# SparkFun_SOIC28-DIP-Adapter-v10.net
KiCad netlist of a schematic drawn in EAGLE
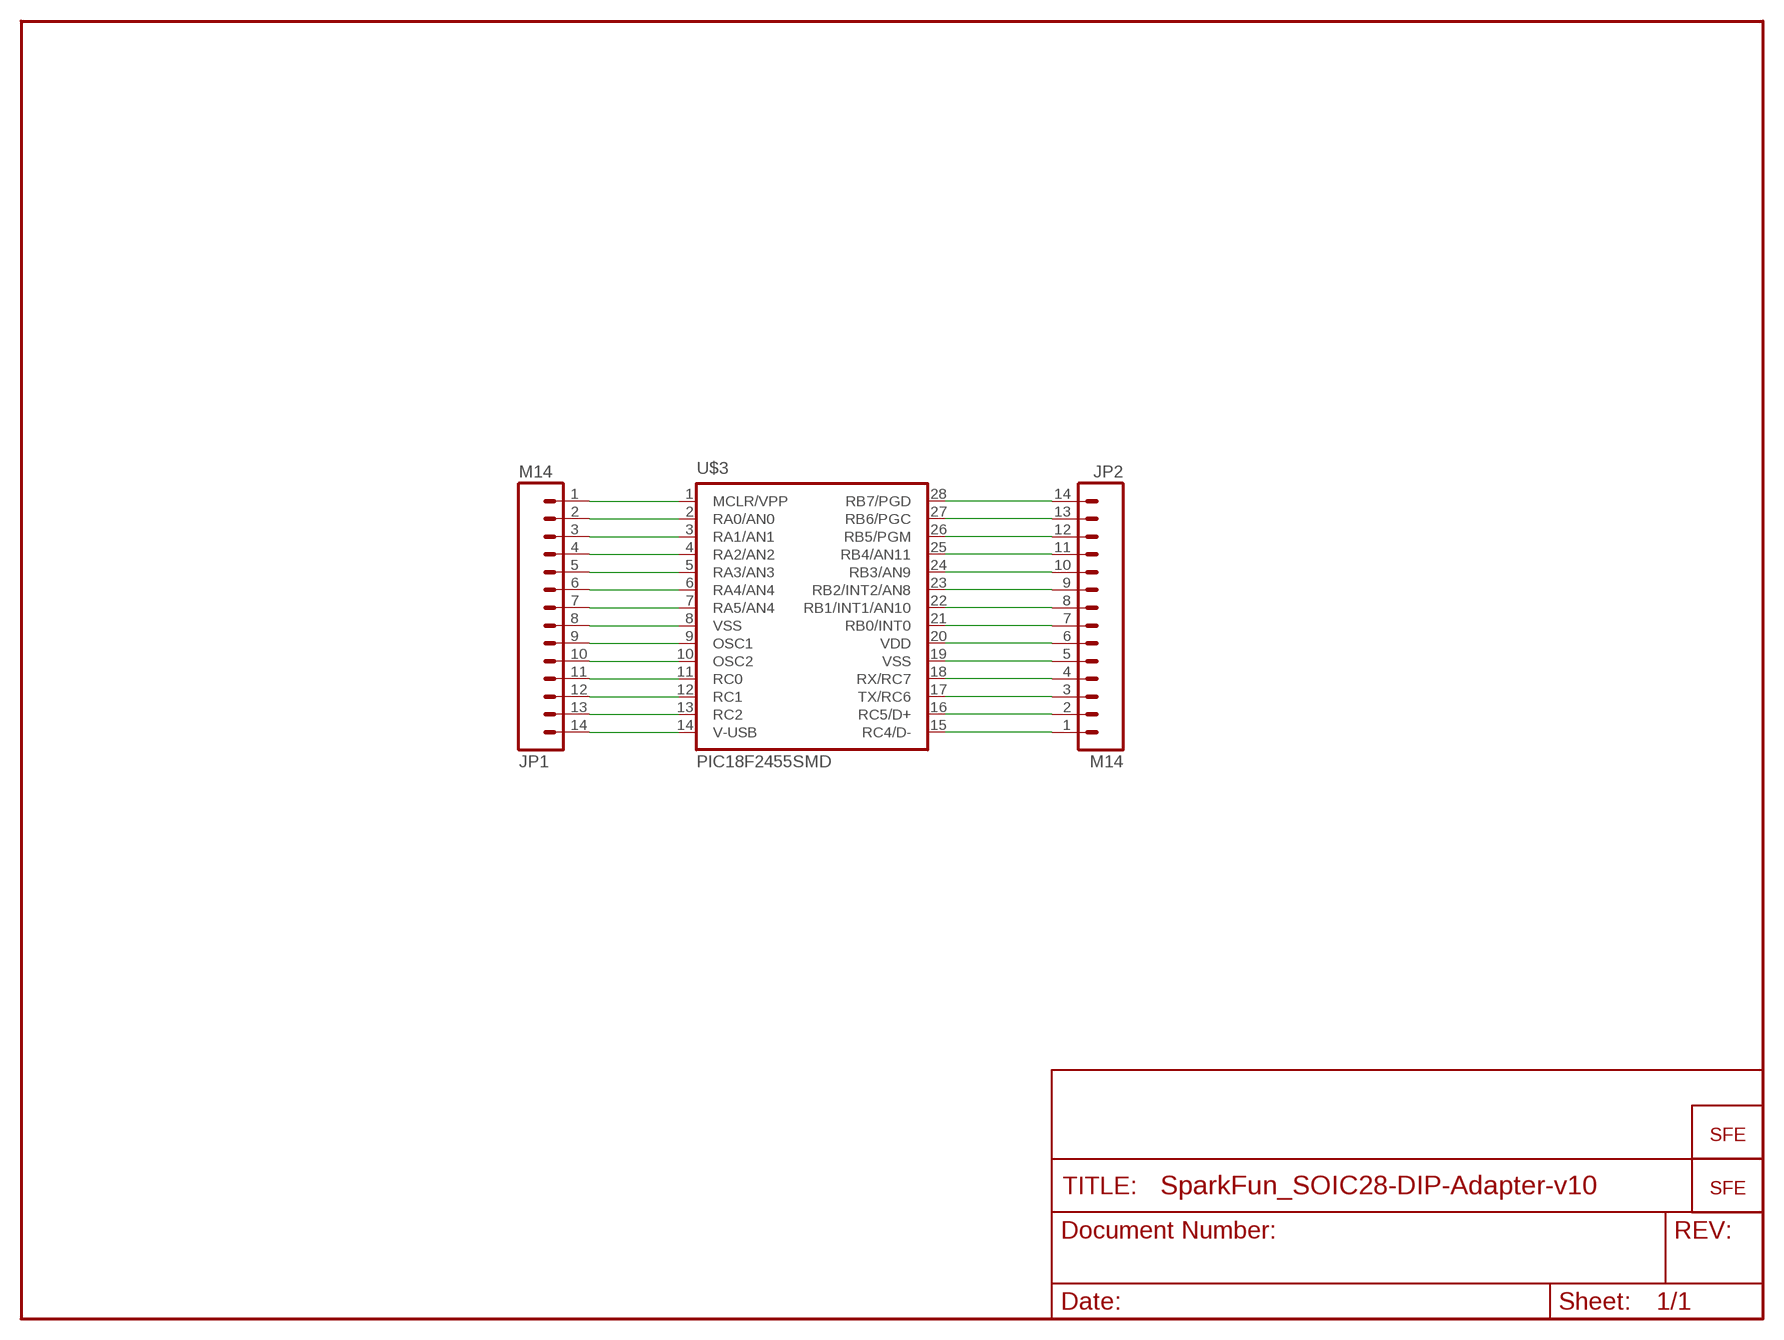
[diagram p0: schematic, sheet 1]

(export (version "E")
  (design (tool "Eeschema 10.0.6"))
  (components
    (comp (ref "JP1")
      (value "M14")
      (footprint "eagle-import:1X14")
      (libsource (lib "eagle-import") (part "M14"))
    )
    (comp (ref "JP2")
      (value "M14")
      (footprint "eagle-import:1X14")
      (libsource (lib "eagle-import") (part "M14"))
    )
    (comp (ref "U$1")
      (value "LOGO-SFESK")
      (footprint "eagle-import:SFE-LOGO-FLAME")
      (libsource (lib "eagle-import") (part "LOGO-SFESK"))
    )
    (comp (ref "U$2")
      (value "LOGO-SFENEW")
      (footprint "eagle-import:SFE-NEW-WEBLOGO")
      (libsource (lib "eagle-import") (part "LOGO-SFENEW"))
    )
    (comp (ref "U$3")
      (value "PIC18F2455SMD")
      (footprint "eagle-import:SO-28W")
      (libsource (lib "eagle-import") (part "PIC18F2455SMD"))
    )
  )
  (nets
    (net (code "1") (name "Net-(JP1-Pad8)") (class "Default")
      (node (ref "JP1") (pin "8") (pinfunction "8_8") (pintype "passive"))
      (node (ref "U$3") (pin "8") (pinfunction "VSS_8") (pintype "power_in"))
    )
    (net (code "2") (name "Net-(JP2-Pad5)") (class "Default")
      (node (ref "JP2") (pin "5") (pinfunction "5_5") (pintype "passive"))
      (node (ref "U$3") (pin "19") (pinfunction "VSS_19") (pintype "power_in"))
    )
    (net (code "3") (name "Net-(U$3-MCLR{slash}VPP)") (class "Default")
      (node (ref "JP1") (pin "1") (pinfunction "1_1") (pintype "passive"))
      (node (ref "U$3") (pin "1") (pinfunction "MCLR/VPP_1") (pintype "bidirectional"))
    )
    (net (code "4") (name "Net-(U$3-OSC1)") (class "Default")
      (node (ref "JP1") (pin "9") (pinfunction "9_9") (pintype "passive"))
      (node (ref "U$3") (pin "9") (pinfunction "OSC1_9") (pintype "bidirectional"))
    )
    (net (code "5") (name "Net-(U$3-OSC2)") (class "Default")
      (node (ref "JP1") (pin "10") (pinfunction "10_10") (pintype "passive"))
      (node (ref "U$3") (pin "10") (pinfunction "OSC2_10") (pintype "bidirectional"))
    )
    (net (code "6") (name "Net-(U$3-RA0{slash}AN0)") (class "Default")
      (node (ref "JP1") (pin "2") (pinfunction "2_2") (pintype "passive"))
      (node (ref "U$3") (pin "2") (pinfunction "RA0/AN0_2") (pintype "bidirectional"))
    )
    (net (code "7") (name "Net-(U$3-RA1{slash}AN1)") (class "Default")
      (node (ref "JP1") (pin "3") (pinfunction "3_3") (pintype "passive"))
      (node (ref "U$3") (pin "3") (pinfunction "RA1/AN1_3") (pintype "bidirectional"))
    )
    (net (code "8") (name "Net-(U$3-RA2{slash}AN2)") (class "Default")
      (node (ref "JP1") (pin "4") (pinfunction "4_4") (pintype "passive"))
      (node (ref "U$3") (pin "4") (pinfunction "RA2/AN2_4") (pintype "bidirectional"))
    )
    (net (code "9") (name "Net-(U$3-RA3{slash}AN3)") (class "Default")
      (node (ref "JP1") (pin "5") (pinfunction "5_5") (pintype "passive"))
      (node (ref "U$3") (pin "5") (pinfunction "RA3/AN3_5") (pintype "bidirectional"))
    )
    (net (code "10") (name "Net-(U$3-RA4{slash}AN4)") (class "Default")
      (node (ref "JP1") (pin "6") (pinfunction "6_6") (pintype "passive"))
      (node (ref "U$3") (pin "6") (pinfunction "RA4/AN4_6") (pintype "bidirectional"))
    )
    (net (code "11") (name "Net-(U$3-RA5{slash}AN4)") (class "Default")
      (node (ref "JP1") (pin "7") (pinfunction "7_7") (pintype "passive"))
      (node (ref "U$3") (pin "7") (pinfunction "RA5/AN4_7") (pintype "bidirectional"))
    )
    (net (code "12") (name "Net-(U$3-RB0{slash}INT0)") (class "Default")
      (node (ref "JP2") (pin "7") (pinfunction "7_7") (pintype "passive"))
      (node (ref "U$3") (pin "21") (pinfunction "RB0/INT0_21") (pintype "bidirectional"))
    )
    (net (code "13") (name "Net-(U$3-RB1{slash}INT1{slash}AN10)") (class "Default")
      (node (ref "JP2") (pin "8") (pinfunction "8_8") (pintype "passive"))
      (node (ref "U$3") (pin "22") (pinfunction "RB1/INT1/AN10_22") (pintype "bidirectional"))
    )
    (net (code "14") (name "Net-(U$3-RB2{slash}INT2{slash}AN8)") (class "Default")
      (node (ref "JP2") (pin "9") (pinfunction "9_9") (pintype "passive"))
      (node (ref "U$3") (pin "23") (pinfunction "RB2/INT2/AN8_23") (pintype "bidirectional"))
    )
    (net (code "15") (name "Net-(U$3-RB3{slash}AN9)") (class "Default")
      (node (ref "JP2") (pin "10") (pinfunction "10_10") (pintype "passive"))
      (node (ref "U$3") (pin "24") (pinfunction "RB3/AN9_24") (pintype "bidirectional"))
    )
    (net (code "16") (name "Net-(U$3-RB4{slash}AN11)") (class "Default")
      (node (ref "JP2") (pin "11") (pinfunction "11_11") (pintype "passive"))
      (node (ref "U$3") (pin "25") (pinfunction "RB4/AN11_25") (pintype "bidirectional"))
    )
    (net (code "17") (name "Net-(U$3-RB5{slash}PGM)") (class "Default")
      (node (ref "JP2") (pin "12") (pinfunction "12_12") (pintype "passive"))
      (node (ref "U$3") (pin "26") (pinfunction "RB5/PGM_26") (pintype "bidirectional"))
    )
    (net (code "18") (name "Net-(U$3-RB6{slash}PGC)") (class "Default")
      (node (ref "JP2") (pin "13") (pinfunction "13_13") (pintype "passive"))
      (node (ref "U$3") (pin "27") (pinfunction "RB6/PGC_27") (pintype "bidirectional"))
    )
    (net (code "19") (name "Net-(U$3-RB7{slash}PGD)") (class "Default")
      (node (ref "JP2") (pin "14") (pinfunction "14_14") (pintype "passive"))
      (node (ref "U$3") (pin "28") (pinfunction "RB7/PGD_28") (pintype "bidirectional"))
    )
    (net (code "20") (name "Net-(U$3-RC0)") (class "Default")
      (node (ref "JP1") (pin "11") (pinfunction "11_11") (pintype "passive"))
      (node (ref "U$3") (pin "11") (pinfunction "RC0_11") (pintype "bidirectional"))
    )
    (net (code "21") (name "Net-(U$3-RC1)") (class "Default")
      (node (ref "JP1") (pin "12") (pinfunction "12_12") (pintype "passive"))
      (node (ref "U$3") (pin "12") (pinfunction "RC1_12") (pintype "bidirectional"))
    )
    (net (code "22") (name "Net-(U$3-RC2)") (class "Default")
      (node (ref "JP1") (pin "13") (pinfunction "13_13") (pintype "passive"))
      (node (ref "U$3") (pin "13") (pinfunction "RC2_13") (pintype "bidirectional"))
    )
    (net (code "23") (name "Net-(U$3-RC4{slash}D-)") (class "Default")
      (node (ref "JP2") (pin "1") (pinfunction "1_1") (pintype "passive"))
      (node (ref "U$3") (pin "15") (pinfunction "RC4/D-_15") (pintype "bidirectional"))
    )
    (net (code "24") (name "Net-(U$3-RC5{slash}D+)") (class "Default")
      (node (ref "JP2") (pin "2") (pinfunction "2_2") (pintype "passive"))
      (node (ref "U$3") (pin "16") (pinfunction "RC5/D+_16") (pintype "bidirectional"))
    )
    (net (code "25") (name "Net-(U$3-RX{slash}RC7)") (class "Default")
      (node (ref "JP2") (pin "4") (pinfunction "4_4") (pintype "passive"))
      (node (ref "U$3") (pin "18") (pinfunction "RX/RC7_18") (pintype "input"))
    )
    (net (code "26") (name "Net-(U$3-TX{slash}RC6)") (class "Default")
      (node (ref "JP2") (pin "3") (pinfunction "3_3") (pintype "passive"))
      (node (ref "U$3") (pin "17") (pinfunction "TX/RC6_17") (pintype "bidirectional"))
    )
    (net (code "27") (name "Net-(U$3-V-USB)") (class "Default")
      (node (ref "JP1") (pin "14") (pinfunction "14_14") (pintype "passive"))
      (node (ref "U$3") (pin "14") (pinfunction "V-USB_14") (pintype "bidirectional"))
    )
    (net (code "28") (name "Net-(U$3-VDD)") (class "Default")
      (node (ref "JP2") (pin "6") (pinfunction "6_6") (pintype "passive"))
      (node (ref "U$3") (pin "20") (pinfunction "VDD_20") (pintype "power_in"))
    )
  )
)
